# LEDSlave.net
KiCad netlist of a schematic drawn in EAGLE
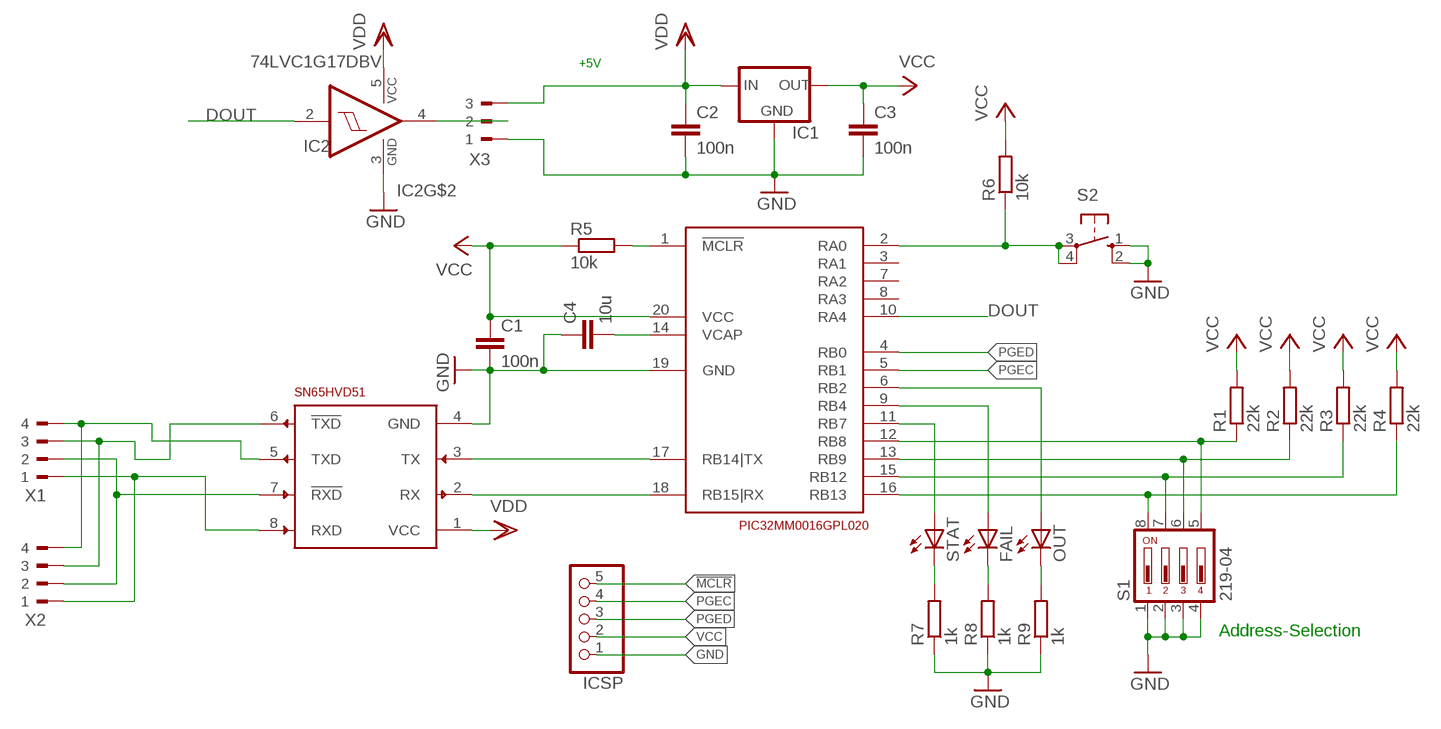
[diagram p0: schematic, sheet 1]

(export (version "E")
  (design (tool "Eeschema 10.0.6"))
  (components
    (comp (ref "C1")
      (value "100n")
      (footprint "eagle-import:C0805")
      (libsource (lib "eagle-import") (part "C-EUC0805"))
    )
    (comp (ref "C2")
      (value "100n")
      (footprint "eagle-import:C0805")
      (libsource (lib "eagle-import") (part "C-EUC0805"))
    )
    (comp (ref "C3")
      (value "100n")
      (footprint "eagle-import:C0805")
      (libsource (lib "eagle-import") (part "C-EUC0805"))
    )
    (comp (ref "C4")
      (value "10u")
      (footprint "eagle-import:C1206")
      (libsource (lib "eagle-import") (part "C-EUC1206"))
    )
    (comp (ref "FAIL")
      (value "LED3MM")
      (footprint "eagle-import:LED3MM")
      (libsource (lib "eagle-import") (part "LED3MM"))
    )
    (comp (ref "IC1")
      (value "LP2950CZ-3.3")
      (footprint "eagle-import:TO92")
      (libsource (lib "eagle-import") (part "LP2950?CZ-3.3"))
    )
    (comp (ref "IC2")
      (value "74LVC1G17DBV")
      (footprint "eagle-import:SOT23-5")
      (libsource (lib "eagle-import") (part "741G17DBVLVC"))
    )
    (comp (ref "ICSP")
      (value "PINHD-1X5")
      (footprint "eagle-import:1X05")
      (libsource (lib "eagle-import") (part "PINHD-1X5"))
    )
    (comp (ref "OUT")
      (value "LED3MM")
      (footprint "eagle-import:LED3MM")
      (libsource (lib "eagle-import") (part "LED3MM"))
    )
    (comp (ref "R1")
      (value "22k")
      (footprint "eagle-import:R0805")
      (libsource (lib "eagle-import") (part "R-EU_R0805"))
    )
    (comp (ref "R2")
      (value "22k")
      (footprint "eagle-import:R0805")
      (libsource (lib "eagle-import") (part "R-EU_R0805"))
    )
    (comp (ref "R3")
      (value "22k")
      (footprint "eagle-import:R0805")
      (libsource (lib "eagle-import") (part "R-EU_R0805"))
    )
    (comp (ref "R4")
      (value "22k")
      (footprint "eagle-import:R0805")
      (libsource (lib "eagle-import") (part "R-EU_R0805"))
    )
    (comp (ref "R5")
      (value "10k")
      (footprint "eagle-import:R0805")
      (libsource (lib "eagle-import") (part "R-EU_R0805"))
    )
    (comp (ref "R6")
      (value "10k")
      (footprint "eagle-import:R0805")
      (libsource (lib "eagle-import") (part "R-EU_R0805"))
    )
    (comp (ref "R7")
      (value "1k")
      (footprint "eagle-import:R0805")
      (libsource (lib "eagle-import") (part "R-EU_R0805"))
    )
    (comp (ref "R8")
      (value "1k")
      (footprint "eagle-import:R0805")
      (libsource (lib "eagle-import") (part "R-EU_R0805"))
    )
    (comp (ref "R9")
      (value "1k")
      (footprint "eagle-import:R0805")
      (libsource (lib "eagle-import") (part "R-EU_R0805"))
    )
    (comp (ref "S1")
      (value "219-04")
      (footprint "eagle-import:CTS-219-04")
      (libsource (lib "eagle-import") (part "219-04"))
    )
    (comp (ref "S2")
      (value "10-XX")
      (footprint "eagle-import:B3F-10XX")
      (fields (field (name "MPN") "B3F-1000"))
      (libsource (lib "eagle-import") (part "10-XX"))
    )
    (comp (ref "STAT")
      (value "LED3MM")
      (footprint "eagle-import:LED3MM")
      (libsource (lib "eagle-import") (part "LED3MM"))
    )
    (comp (ref "U$1")
      (value "PIC32MM0016GPL020")
      (footprint "eagle-import:SSOP20")
      (libsource (lib "eagle-import") (part "PIC32MM0016GPL020"))
    )
    (comp (ref "U$2")
      (value "SN65HVD51")
      (footprint "eagle-import:SO-08")
      (libsource (lib "eagle-import") (part "SN65HVD51"))
    )
    (comp (ref "X1")
      (value "90-4")
      (footprint "eagle-import:90-4")
      (libsource (lib "eagle-import") (part "90-4"))
    )
    (comp (ref "X2")
      (value "90-4")
      (footprint "eagle-import:90-4")
      (libsource (lib "eagle-import") (part "90-4"))
    )
    (comp (ref "X3")
      (value "90-3")
      (footprint "eagle-import:90-3")
      (libsource (lib "eagle-import") (part "90-3"))
    )
  )
  (nets
    (net (code "1") (name "/DOUT") (class "Default")
      (node (ref "IC2") (pin "2") (pinfunction "I_2") (pintype "input"))
      (node (ref "U$1") (pin "10") (pinfunction "RA4_10") (pintype "bidirectional"))
    )
    (net (code "2") (name "/~{MCLR}") (class "Default")
      (node (ref "ICSP") (pin "5") (pinfunction "5_5") (pintype "passive"))
      (node (ref "R5") (pin "2") (pinfunction "2_2") (pintype "passive"))
      (node (ref "U$1") (pin "1") (pinfunction "~{MCLR}_1") (pintype "bidirectional"))
    )
    (net (code "3") (name "GND") (class "Default")
      (node (ref "C1") (pin "2") (pinfunction "2_2") (pintype "passive"))
      (node (ref "C2") (pin "2") (pinfunction "2_2") (pintype "passive"))
      (node (ref "C3") (pin "2") (pinfunction "2_2") (pintype "passive"))
      (node (ref "C4") (pin "1") (pinfunction "1_1") (pintype "passive"))
      (node (ref "IC1") (pin "2") (pinfunction "GND_2") (pintype "input"))
      (node (ref "IC2") (pin "3") (pinfunction "GND_3") (pintype "power_in"))
      (node (ref "ICSP") (pin "1") (pinfunction "1_1") (pintype "passive"))
      (node (ref "R7") (pin "1") (pinfunction "1_1") (pintype "passive"))
      (node (ref "R8") (pin "1") (pinfunction "1_1") (pintype "passive"))
      (node (ref "R9") (pin "1") (pinfunction "1_1") (pintype "passive"))
      (node (ref "S1") (pin "1") (pinfunction "1_1") (pintype "passive"))
      (node (ref "S1") (pin "2") (pinfunction "2_2") (pintype "passive"))
      (node (ref "S1") (pin "3") (pinfunction "3_3") (pintype "passive"))
      (node (ref "S1") (pin "4") (pinfunction "4_4") (pintype "passive"))
      (node (ref "S2") (pin "1") (pinfunction "S_1") (pintype "passive"))
      (node (ref "S2") (pin "2") (pinfunction "S1_2") (pintype "passive"))
      (node (ref "U$1") (pin "19") (pinfunction "GND_19") (pintype "bidirectional"))
      (node (ref "U$2") (pin "4") (pinfunction "GND_4") (pintype "bidirectional"))
      (node (ref "X3") (pin "1") (pinfunction "1_1") (pintype "passive"))
    )
    (net (code "4") (name "Net-(FAIL-C)") (class "Default")
      (node (ref "FAIL") (pin "K") (pinfunction "C_K") (pintype "passive"))
      (node (ref "R8") (pin "2") (pinfunction "2_2") (pintype "passive"))
    )
    (net (code "5") (name "Net-(IC2A-O)") (class "Default")
      (node (ref "IC2") (pin "4") (pinfunction "O_4") (pintype "output"))
      (node (ref "X3") (pin "2") (pinfunction "2_2") (pintype "passive"))
    )
    (net (code "6") (name "Net-(OUT-C)") (class "Default")
      (node (ref "OUT") (pin "K") (pinfunction "C_K") (pintype "passive"))
      (node (ref "R9") (pin "2") (pinfunction "2_2") (pintype "passive"))
    )
    (net (code "7") (name "Net-(S2-P)") (class "Default")
      (node (ref "R6") (pin "1") (pinfunction "1_1") (pintype "passive"))
      (node (ref "S2") (pin "3") (pinfunction "P_3") (pintype "passive"))
      (node (ref "S2") (pin "4") (pinfunction "P1_4") (pintype "passive"))
      (node (ref "U$1") (pin "2") (pinfunction "RA0_2") (pintype "bidirectional"))
    )
    (net (code "8") (name "Net-(STAT-C)") (class "Default")
      (node (ref "R7") (pin "2") (pinfunction "2_2") (pintype "passive"))
      (node (ref "STAT") (pin "K") (pinfunction "C_K") (pintype "passive"))
    )
    (net (code "9") (name "Net-(U$1-RB2)") (class "Default")
      (node (ref "OUT") (pin "A") (pinfunction "A_A") (pintype "passive"))
      (node (ref "U$1") (pin "6") (pinfunction "RB2_6") (pintype "bidirectional"))
    )
    (net (code "10") (name "Net-(U$1-RB4)") (class "Default")
      (node (ref "FAIL") (pin "A") (pinfunction "A_A") (pintype "passive"))
      (node (ref "U$1") (pin "9") (pinfunction "RB4_9") (pintype "bidirectional"))
    )
    (net (code "11") (name "Net-(U$1-RB7)") (class "Default")
      (node (ref "STAT") (pin "A") (pinfunction "A_A") (pintype "passive"))
      (node (ref "U$1") (pin "11") (pinfunction "RB7_11") (pintype "bidirectional"))
    )
    (net (code "12") (name "Net-(U$1-RB8)") (class "Default")
      (node (ref "R1") (pin "1") (pinfunction "1_1") (pintype "passive"))
      (node (ref "S1") (pin "5") (pinfunction "5_5") (pintype "passive"))
      (node (ref "U$1") (pin "12") (pinfunction "RB8_12") (pintype "bidirectional"))
    )
    (net (code "13") (name "Net-(U$1-RB9)") (class "Default")
      (node (ref "R2") (pin "1") (pinfunction "1_1") (pintype "passive"))
      (node (ref "S1") (pin "6") (pinfunction "6_6") (pintype "passive"))
      (node (ref "U$1") (pin "13") (pinfunction "RB9_13") (pintype "bidirectional"))
    )
    (net (code "14") (name "Net-(U$1-RB12)") (class "Default")
      (node (ref "R3") (pin "1") (pinfunction "1_1") (pintype "passive"))
      (node (ref "S1") (pin "7") (pinfunction "7_7") (pintype "passive"))
      (node (ref "U$1") (pin "15") (pinfunction "RB12_15") (pintype "bidirectional"))
    )
    (net (code "15") (name "Net-(U$1-RB13)") (class "Default")
      (node (ref "R4") (pin "1") (pinfunction "1_1") (pintype "passive"))
      (node (ref "S1") (pin "8") (pinfunction "8_8") (pintype "passive"))
      (node (ref "U$1") (pin "16") (pinfunction "RB13_16") (pintype "bidirectional"))
    )
    (net (code "16") (name "Net-(U$1-RB14|TX)") (class "Default")
      (node (ref "U$1") (pin "17") (pinfunction "RB14|TX_17") (pintype "bidirectional"))
      (node (ref "U$2") (pin "3") (pinfunction "TX_3") (pintype "bidirectional"))
    )
    (net (code "17") (name "Net-(U$1-RB15|RX)") (class "Default")
      (node (ref "U$1") (pin "18") (pinfunction "RB15|RX_18") (pintype "bidirectional"))
      (node (ref "U$2") (pin "2") (pinfunction "RX_2") (pintype "bidirectional"))
    )
    (net (code "18") (name "Net-(U$1-VCAP)") (class "Default")
      (node (ref "C4") (pin "2") (pinfunction "2_2") (pintype "passive"))
      (node (ref "U$1") (pin "14") (pinfunction "VCAP_14") (pintype "bidirectional"))
    )
    (net (code "19") (name "Net-(U$2-RXD)") (class "Default")
      (node (ref "U$2") (pin "8") (pinfunction "RXD_8") (pintype "bidirectional"))
      (node (ref "X1") (pin "1") (pinfunction "1_1") (pintype "passive"))
      (node (ref "X2") (pin "1") (pinfunction "1_1") (pintype "passive"))
    )
    (net (code "20") (name "Net-(U$2-TXD)") (class "Default")
      (node (ref "U$2") (pin "5") (pinfunction "TXD_5") (pintype "bidirectional"))
      (node (ref "X1") (pin "4") (pinfunction "4_4") (pintype "passive"))
      (node (ref "X2") (pin "4") (pinfunction "4_4") (pintype "passive"))
    )
    (net (code "21") (name "Net-(U$2-~{RXD})") (class "Default")
      (node (ref "U$2") (pin "7") (pinfunction "~{RXD}_7") (pintype "bidirectional"))
      (node (ref "X1") (pin "2") (pinfunction "2_2") (pintype "passive"))
      (node (ref "X2") (pin "2") (pinfunction "2_2") (pintype "passive"))
    )
    (net (code "22") (name "Net-(U$2-~{TXD})") (class "Default")
      (node (ref "U$2") (pin "6") (pinfunction "~{TXD}_6") (pintype "bidirectional"))
      (node (ref "X1") (pin "3") (pinfunction "3_3") (pintype "passive"))
      (node (ref "X2") (pin "3") (pinfunction "3_3") (pintype "passive"))
    )
    (net (code "23") (name "PGEC") (class "Default")
      (node (ref "ICSP") (pin "4") (pinfunction "4_4") (pintype "passive"))
      (node (ref "U$1") (pin "5") (pinfunction "RB1_5") (pintype "bidirectional"))
    )
    (net (code "24") (name "PGED") (class "Default")
      (node (ref "ICSP") (pin "3") (pinfunction "3_3") (pintype "passive"))
      (node (ref "U$1") (pin "4") (pinfunction "RB0_4") (pintype "bidirectional"))
    )
    (net (code "25") (name "VCC") (class "Default")
      (node (ref "C1") (pin "1") (pinfunction "1_1") (pintype "passive"))
      (node (ref "C3") (pin "1") (pinfunction "1_1") (pintype "passive"))
      (node (ref "IC1") (pin "1") (pinfunction "OUT_1") (pintype "passive"))
      (node (ref "ICSP") (pin "2") (pinfunction "2_2") (pintype "passive"))
      (node (ref "R1") (pin "2") (pinfunction "2_2") (pintype "passive"))
      (node (ref "R2") (pin "2") (pinfunction "2_2") (pintype "passive"))
      (node (ref "R3") (pin "2") (pinfunction "2_2") (pintype "passive"))
      (node (ref "R4") (pin "2") (pinfunction "2_2") (pintype "passive"))
      (node (ref "R5") (pin "1") (pinfunction "1_1") (pintype "passive"))
      (node (ref "R6") (pin "2") (pinfunction "2_2") (pintype "passive"))
      (node (ref "U$1") (pin "20") (pinfunction "VCC_20") (pintype "bidirectional"))
    )
    (net (code "26") (name "VDD") (class "Default")
      (node (ref "C2") (pin "1") (pinfunction "1_1") (pintype "passive"))
      (node (ref "IC1") (pin "3") (pinfunction "IN_3") (pintype "input"))
      (node (ref "IC2") (pin "5") (pinfunction "VCC_5") (pintype "power_in"))
      (node (ref "U$2") (pin "1") (pinfunction "VCC_1") (pintype "bidirectional"))
      (node (ref "X3") (pin "3") (pinfunction "3_3") (pintype "passive"))
    )
    (net (code "27") (name "unconnected-(U$1-RA1-Pad3)") (class "Default")
      (node (ref "U$1") (pin "3") (pinfunction "RA1_3") (pintype "bidirectional"))
    )
    (net (code "28") (name "unconnected-(U$1-RA2-Pad7)") (class "Default")
      (node (ref "U$1") (pin "7") (pinfunction "RA2_7") (pintype "bidirectional"))
    )
    (net (code "29") (name "unconnected-(U$1-RA3-Pad8)") (class "Default")
      (node (ref "U$1") (pin "8") (pinfunction "RA3_8") (pintype "bidirectional"))
    )
  )
)
